# FPGA_misc.net
KiCad netlist of a schematic drawn in Altium Designer
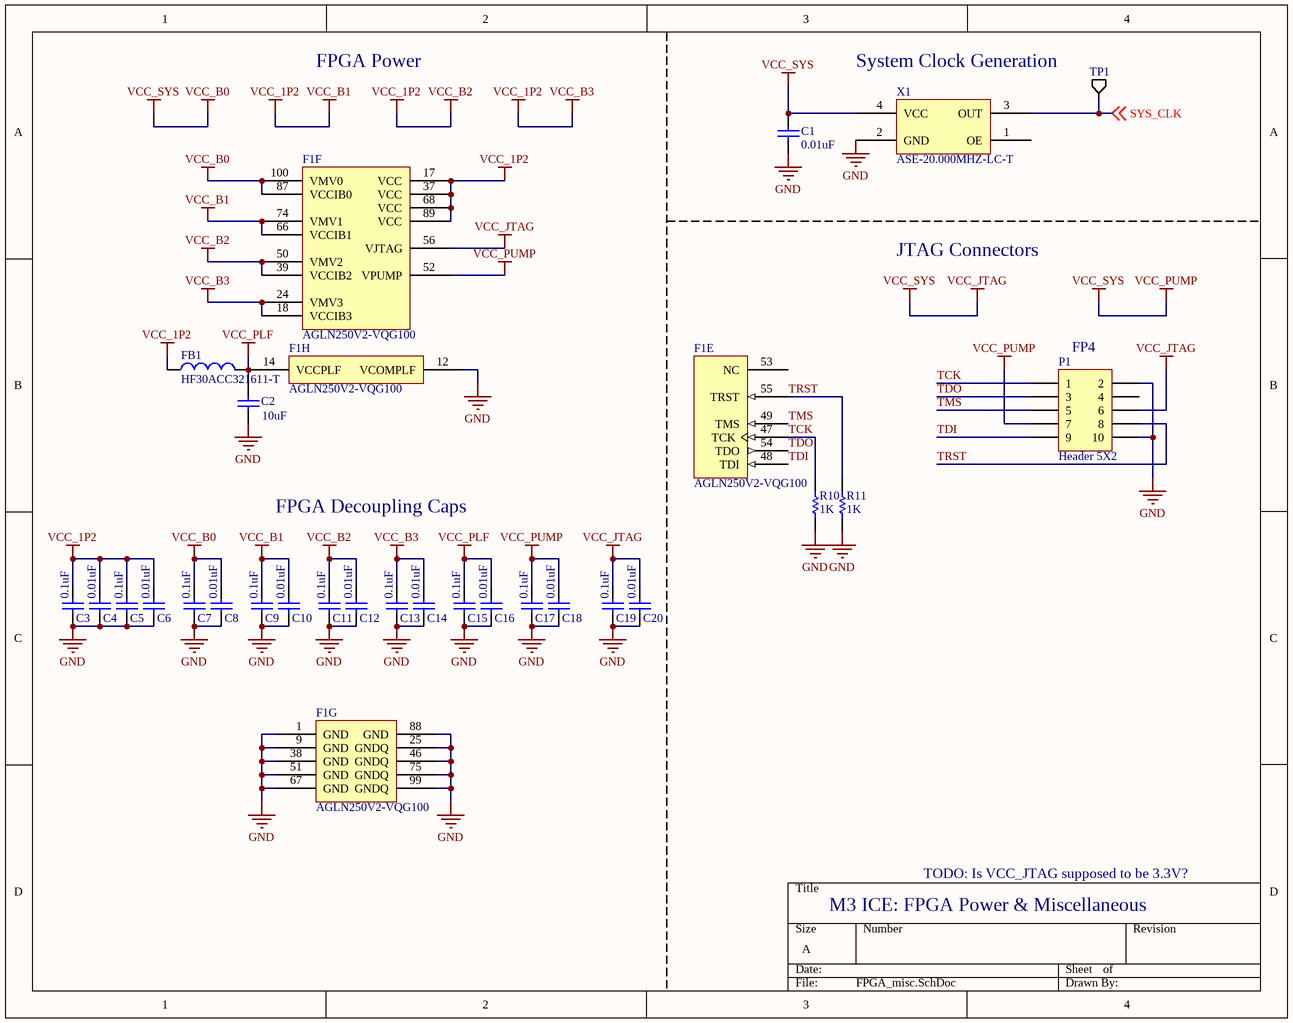
[diagram p0: FPGA_misc.SchDoc]

(export (version "E")
  (design (tool "Eeschema 10.0.6"))
  (components
    (comp (ref "C1")
      (value "0.01uF")
      (footprint "1608[0603]")
      (description "Capacitor (Semiconductor SIM Model)")
      (fields
        (field (name "DISTPARTNO") "445-1311-1-ND")
        (field (name "MANPARTNO") "C1608X7R1H103K")
        (field (name "PUBLISHER") "Altium Limited")
      )
      (libsource (lib "Miscellaneous Devices") (part "Cap Semi"))
    )
    (comp (ref "C2")
      (value "10uF")
      (footprint "0805")
      (description "Capacitor (Semiconductor SIM Model)")
      (fields
        (field (name "DISTPARTNO") "445-7645-1-ND")
        (field (name "MANPARTNO") "C2012X5R1C106M/0.85")
        (field (name "PUBLISHER") "Altium Limited")
      )
      (libsource (lib "M3") (part "Cap Chip"))
    )
    (comp (ref "C3")
      (value "0.1uF")
      (footprint "1608[0603]")
      (description "Capacitor (Semiconductor SIM Model)")
      (fields
        (field (name "DISTPARTNO") "445-1317-1-ND")
        (field (name "MANPARTNO") "C1608X7R1C104K")
        (field (name "PUBLISHER") "Altium Limited")
      )
      (libsource (lib "Miscellaneous Devices") (part "Cap Semi"))
    )
    (comp (ref "C4")
      (value "0.01uF")
      (footprint "1608[0603]")
      (description "Capacitor (Semiconductor SIM Model)")
      (fields
        (field (name "DISTPARTNO") "445-1311-1-ND")
        (field (name "MANPARTNO") "C1608X7R1H103K")
        (field (name "PUBLISHER") "Altium Limited")
      )
      (libsource (lib "Miscellaneous Devices") (part "Cap Semi"))
    )
    (comp (ref "C5")
      (value "0.1uF")
      (footprint "1608[0603]")
      (description "Capacitor (Semiconductor SIM Model)")
      (fields
        (field (name "DISTPARTNO") "445-1317-1-ND")
        (field (name "MANPARTNO") "C1608X7R1C104K")
        (field (name "PUBLISHER") "Altium Limited")
      )
      (libsource (lib "Miscellaneous Devices") (part "Cap Semi"))
    )
    (comp (ref "C6")
      (value "0.01uF")
      (footprint "1608[0603]")
      (description "Capacitor (Semiconductor SIM Model)")
      (fields
        (field (name "DISTPARTNO") "445-1311-1-ND")
        (field (name "MANPARTNO") "C1608X7R1H103K")
        (field (name "PUBLISHER") "Altium Limited")
      )
      (libsource (lib "Miscellaneous Devices") (part "Cap Semi"))
    )
    (comp (ref "C7")
      (value "0.1uF")
      (footprint "1608[0603]")
      (description "Capacitor (Semiconductor SIM Model)")
      (fields
        (field (name "DISTPARTNO") "445-1317-1-ND")
        (field (name "MANPARTNO") "C1608X7R1C104K")
        (field (name "PUBLISHER") "Altium Limited")
      )
      (libsource (lib "Miscellaneous Devices") (part "Cap Semi"))
    )
    (comp (ref "C8")
      (value "0.01uF")
      (footprint "1608[0603]")
      (description "Capacitor (Semiconductor SIM Model)")
      (fields
        (field (name "DISTPARTNO") "445-1311-1-ND")
        (field (name "MANPARTNO") "C1608X7R1H103K")
        (field (name "PUBLISHER") "Altium Limited")
      )
      (libsource (lib "Miscellaneous Devices") (part "Cap Semi"))
    )
    (comp (ref "C9")
      (value "0.1uF")
      (footprint "1608[0603]")
      (description "Capacitor (Semiconductor SIM Model)")
      (fields
        (field (name "DISTPARTNO") "445-1317-1-ND")
        (field (name "MANPARTNO") "C1608X7R1C104K")
        (field (name "PUBLISHER") "Altium Limited")
      )
      (libsource (lib "Miscellaneous Devices") (part "Cap Semi"))
    )
    (comp (ref "C10")
      (value "0.01uF")
      (footprint "1608[0603]")
      (description "Capacitor (Semiconductor SIM Model)")
      (fields
        (field (name "DISTPARTNO") "445-1311-1-ND")
        (field (name "MANPARTNO") "C1608X7R1H103K")
        (field (name "PUBLISHER") "Altium Limited")
      )
      (libsource (lib "Miscellaneous Devices") (part "Cap Semi"))
    )
    (comp (ref "C11")
      (value "0.1uF")
      (footprint "1608[0603]")
      (description "Capacitor (Semiconductor SIM Model)")
      (fields
        (field (name "DISTPARTNO") "445-1317-1-ND")
        (field (name "MANPARTNO") "C1608X7R1C104K")
        (field (name "PUBLISHER") "Altium Limited")
      )
      (libsource (lib "Miscellaneous Devices") (part "Cap Semi"))
    )
    (comp (ref "C12")
      (value "0.01uF")
      (footprint "1608[0603]")
      (description "Capacitor (Semiconductor SIM Model)")
      (fields
        (field (name "DISTPARTNO") "445-1311-1-ND")
        (field (name "MANPARTNO") "C1608X7R1H103K")
        (field (name "PUBLISHER") "Altium Limited")
      )
      (libsource (lib "Miscellaneous Devices") (part "Cap Semi"))
    )
    (comp (ref "C13")
      (value "0.1uF")
      (footprint "1608[0603]")
      (description "Capacitor (Semiconductor SIM Model)")
      (fields
        (field (name "DISTPARTNO") "445-1317-1-ND")
        (field (name "MANPARTNO") "C1608X7R1C104K")
        (field (name "PUBLISHER") "Altium Limited")
      )
      (libsource (lib "Miscellaneous Devices") (part "Cap Semi"))
    )
    (comp (ref "C14")
      (value "0.01uF")
      (footprint "1608[0603]")
      (description "Capacitor (Semiconductor SIM Model)")
      (fields
        (field (name "DISTPARTNO") "445-1311-1-ND")
        (field (name "MANPARTNO") "C1608X7R1H103K")
        (field (name "PUBLISHER") "Altium Limited")
      )
      (libsource (lib "Miscellaneous Devices") (part "Cap Semi"))
    )
    (comp (ref "C15")
      (value "0.1uF")
      (footprint "1608[0603]")
      (description "Capacitor (Semiconductor SIM Model)")
      (fields
        (field (name "DISTPARTNO") "445-1317-1-ND")
        (field (name "MANPARTNO") "C1608X7R1C104K")
        (field (name "PUBLISHER") "Altium Limited")
      )
      (libsource (lib "Miscellaneous Devices") (part "Cap Semi"))
    )
    (comp (ref "C16")
      (value "0.01uF")
      (footprint "1608[0603]")
      (description "Capacitor (Semiconductor SIM Model)")
      (fields
        (field (name "DISTPARTNO") "445-1311-1-ND")
        (field (name "MANPARTNO") "C1608X7R1H103K")
        (field (name "PUBLISHER") "Altium Limited")
      )
      (libsource (lib "Miscellaneous Devices") (part "Cap Semi"))
    )
    (comp (ref "C17")
      (value "0.1uF")
      (footprint "1608[0603]")
      (description "Capacitor (Semiconductor SIM Model)")
      (fields
        (field (name "DISTPARTNO") "445-1317-1-ND")
        (field (name "MANPARTNO") "C1608X7R1C104K")
        (field (name "PUBLISHER") "Altium Limited")
      )
      (libsource (lib "Miscellaneous Devices") (part "Cap Semi"))
    )
    (comp (ref "C18")
      (value "0.01uF")
      (footprint "1608[0603]")
      (description "Capacitor (Semiconductor SIM Model)")
      (fields
        (field (name "DISTPARTNO") "445-1311-1-ND")
        (field (name "MANPARTNO") "C1608X7R1H103K")
        (field (name "PUBLISHER") "Altium Limited")
      )
      (libsource (lib "Miscellaneous Devices") (part "Cap Semi"))
    )
    (comp (ref "C19")
      (value "0.1uF")
      (footprint "1608[0603]")
      (description "Capacitor (Semiconductor SIM Model)")
      (fields
        (field (name "DISTPARTNO") "445-1317-1-ND")
        (field (name "MANPARTNO") "C1608X7R1C104K")
        (field (name "PUBLISHER") "Altium Limited")
      )
      (libsource (lib "Miscellaneous Devices") (part "Cap Semi"))
    )
    (comp (ref "C20")
      (value "0.01uF")
      (footprint "1608[0603]")
      (description "Capacitor (Semiconductor SIM Model)")
      (fields
        (field (name "DISTPARTNO") "445-1311-1-ND")
        (field (name "MANPARTNO") "C1608X7R1H103K")
        (field (name "PUBLISHER") "Altium Limited")
      )
      (libsource (lib "Miscellaneous Devices") (part "Cap Semi"))
    )
    (comp (ref "F1")
      (value "AGLN250V2-VQG100")
      (footprint "VQ100_N")
      (fields (field (name "DISTPARTNO") "1100-1134-ND") (field (name "PUBLISHER") "Altium Limited"))
      (libsource (lib "") (part "AGLN250V2-VQG100_1"))
    )
    (comp (ref "FB1")
      (value "HF30ACC321611-T")
      (footprint "Ferrite_Bead_3.2mm_1.6mm")
      (fields (field (name "DISTPARTNO") "445-6165-1-ND"))
      (libsource (lib "M3") (part "Ferrite Bead HF30ACC321611-T"))
    )
    (comp (ref "P1")
      (value "Header 5X2")
      (footprint "HDR2X5")
      (description "Header, 5-Pin, Dual row")
      (fields (field (name "PUBLISHER") "Altium Limited"))
      (libsource (lib "Miscellaneous Connectors") (part "Header 5X2"))
    )
    (comp (ref "R10")
      (value "1K")
      (footprint "0603")
      (description "Semiconductor Resistor")
      (fields
        (field (name "DISTPARTNO") "P1.0KGCT-ND")
        (field (name "MANPARTNO") "ERJ-3GEYJ102V")
        (field (name "PUBLISHER") "Altium Limited")
      )
      (libsource (lib "M3") (part "Res Chip"))
    )
    (comp (ref "R11")
      (value "1K")
      (footprint "0603")
      (description "Semiconductor Resistor")
      (fields
        (field (name "DISTPARTNO") "P1.0KGCT-ND")
        (field (name "MANPARTNO") "ERJ-3GEYJ102V")
        (field (name "PUBLISHER") "Altium Limited")
      )
      (libsource (lib "M3") (part "Res Chip"))
    )
    (comp (ref "TP1") (value "TP") (footprint "TP") (libsource (lib "M3") (part "TP")))
    (comp (ref "X1")
      (value "ASE-20.000MHZ-LC-T")
      (footprint "CRYSTAL_3.2mm_2.5mm")
      (fields (field (name "DISTPARTNO") "535-9565-1-ND"))
      (libsource (lib "M3") (part "ASE-20.000MHZ-LC-T"))
    )
  )
  (nets
    (net (code "1") (name "/TCK") (class "Default")
      (node (ref "F1") (pin "47") (pinfunction "TCK_47") (pintype "input"))
      (node (ref "P1") (pin "1") (pinfunction "1_1") (pintype "passive"))
      (node (ref "R10") (pin "1") (pinfunction "1_1") (pintype "passive"))
    )
    (net (code "2") (name "/TDI") (class "Default")
      (node (ref "F1") (pin "48") (pinfunction "TDI_48") (pintype "input"))
      (node (ref "P1") (pin "9") (pinfunction "9_9") (pintype "passive"))
    )
    (net (code "3") (name "/TDO") (class "Default")
      (node (ref "F1") (pin "54") (pinfunction "TDO_54") (pintype "output"))
      (node (ref "P1") (pin "3") (pinfunction "3_3") (pintype "passive"))
    )
    (net (code "4") (name "/TMS") (class "Default")
      (node (ref "F1") (pin "49") (pinfunction "TMS_49") (pintype "input"))
      (node (ref "P1") (pin "5") (pinfunction "5_5") (pintype "passive"))
    )
    (net (code "5") (name "/TRST") (class "Default")
      (node (ref "F1") (pin "55") (pinfunction "TRST_55") (pintype "input"))
      (node (ref "P1") (pin "8") (pinfunction "8_8") (pintype "passive"))
      (node (ref "R11") (pin "1") (pinfunction "1_1") (pintype "passive"))
    )
    (net (code "6") (name "GND") (class "Default")
      (node (ref "C1") (pin "1") (pinfunction "1_1") (pintype "passive"))
      (node (ref "C10") (pin "1") (pinfunction "1_1") (pintype "passive"))
      (node (ref "C11") (pin "1") (pinfunction "1_1") (pintype "passive"))
      (node (ref "C12") (pin "1") (pinfunction "1_1") (pintype "passive"))
      (node (ref "C13") (pin "1") (pinfunction "1_1") (pintype "passive"))
      (node (ref "C14") (pin "1") (pinfunction "1_1") (pintype "passive"))
      (node (ref "C15") (pin "1") (pinfunction "1_1") (pintype "passive"))
      (node (ref "C16") (pin "1") (pinfunction "1_1") (pintype "passive"))
      (node (ref "C17") (pin "1") (pinfunction "1_1") (pintype "passive"))
      (node (ref "C18") (pin "1") (pinfunction "1_1") (pintype "passive"))
      (node (ref "C19") (pin "1") (pinfunction "1_1") (pintype "passive"))
      (node (ref "C2") (pin "1") (pinfunction "1_1") (pintype "passive"))
      (node (ref "C20") (pin "1") (pinfunction "1_1") (pintype "passive"))
      (node (ref "C3") (pin "1") (pinfunction "1_1") (pintype "passive"))
      (node (ref "C4") (pin "1") (pinfunction "1_1") (pintype "passive"))
      (node (ref "C5") (pin "1") (pinfunction "1_1") (pintype "passive"))
      (node (ref "C6") (pin "1") (pinfunction "1_1") (pintype "passive"))
      (node (ref "C7") (pin "1") (pinfunction "1_1") (pintype "passive"))
      (node (ref "C8") (pin "1") (pinfunction "1_1") (pintype "passive"))
      (node (ref "C9") (pin "1") (pinfunction "1_1") (pintype "passive"))
      (node (ref "F1") (pin "1") (pinfunction "GND_1") (pintype "power_in"))
      (node (ref "F1") (pin "12") (pinfunction "VCOMPLF_12") (pintype "power_in"))
      (node (ref "F1") (pin "25") (pinfunction "GNDQ_25") (pintype "power_in"))
      (node (ref "F1") (pin "38") (pinfunction "GND_38") (pintype "power_in"))
      (node (ref "F1") (pin "46") (pinfunction "GNDQ_46") (pintype "power_in"))
      (node (ref "F1") (pin "51") (pinfunction "GND_51") (pintype "power_in"))
      (node (ref "F1") (pin "67") (pinfunction "GND_67") (pintype "power_in"))
      (node (ref "F1") (pin "75") (pinfunction "GNDQ_75") (pintype "power_in"))
      (node (ref "F1") (pin "88") (pinfunction "GND_88") (pintype "power_in"))
      (node (ref "F1") (pin "9") (pinfunction "GND_9") (pintype "power_in"))
      (node (ref "F1") (pin "99") (pinfunction "GNDQ_99") (pintype "power_in"))
      (node (ref "P1") (pin "10") (pinfunction "10_10") (pintype "passive"))
      (node (ref "P1") (pin "2") (pinfunction "2_2") (pintype "passive"))
      (node (ref "R10") (pin "2") (pinfunction "2_2") (pintype "passive"))
      (node (ref "R11") (pin "2") (pinfunction "2_2") (pintype "passive"))
      (node (ref "X1") (pin "2") (pinfunction "GND_2") (pintype "passive"))
    )
    (net (code "7") (name "SYS_CLK") (class "Default")
      (node (ref "TP1") (pin "1") (pinfunction "A_1") (pintype "passive"))
      (node (ref "X1") (pin "3") (pinfunction "OUT_3") (pintype "passive"))
    )
    (net (code "8") (name "VCC_1P2") (class "Default")
      (node (ref "C10") (pin "2") (pinfunction "2_2") (pintype "passive"))
      (node (ref "C11") (pin "2") (pinfunction "2_2") (pintype "passive"))
      (node (ref "C12") (pin "2") (pinfunction "2_2") (pintype "passive"))
      (node (ref "C13") (pin "2") (pinfunction "2_2") (pintype "passive"))
      (node (ref "C14") (pin "2") (pinfunction "2_2") (pintype "passive"))
      (node (ref "C3") (pin "2") (pinfunction "2_2") (pintype "passive"))
      (node (ref "C4") (pin "2") (pinfunction "2_2") (pintype "passive"))
      (node (ref "C5") (pin "2") (pinfunction "2_2") (pintype "passive"))
      (node (ref "C6") (pin "2") (pinfunction "2_2") (pintype "passive"))
      (node (ref "C9") (pin "2") (pinfunction "2_2") (pintype "passive"))
      (node (ref "F1") (pin "17") (pinfunction "VCC_17") (pintype "power_in"))
      (node (ref "F1") (pin "18") (pinfunction "VCCIB3_18") (pintype "power_in"))
      (node (ref "F1") (pin "24") (pinfunction "VMV3_24") (pintype "power_in"))
      (node (ref "F1") (pin "37") (pinfunction "VCC_37") (pintype "power_in"))
      (node (ref "F1") (pin "39") (pinfunction "VCCIB2_39") (pintype "power_in"))
      (node (ref "F1") (pin "50") (pinfunction "VMV2_50") (pintype "power_in"))
      (node (ref "F1") (pin "66") (pinfunction "VCCIB1_66") (pintype "power_in"))
      (node (ref "F1") (pin "68") (pinfunction "VCC_68") (pintype "power_in"))
      (node (ref "F1") (pin "74") (pinfunction "VMV1_74") (pintype "power_in"))
      (node (ref "F1") (pin "89") (pinfunction "VCC_89") (pintype "power_in"))
      (node (ref "FB1") (pin "1") (pinfunction "1_1") (pintype "passive"))
    )
    (net (code "9") (name "VCC_B0") (class "Default")
      (node (ref "C1") (pin "2") (pinfunction "2_2") (pintype "passive"))
      (node (ref "C17") (pin "2") (pinfunction "2_2") (pintype "passive"))
      (node (ref "C18") (pin "2") (pinfunction "2_2") (pintype "passive"))
      (node (ref "C19") (pin "2") (pinfunction "2_2") (pintype "passive"))
      (node (ref "C20") (pin "2") (pinfunction "2_2") (pintype "passive"))
      (node (ref "C7") (pin "2") (pinfunction "2_2") (pintype "passive"))
      (node (ref "C8") (pin "2") (pinfunction "2_2") (pintype "passive"))
      (node (ref "F1") (pin "100") (pinfunction "VMV0_100") (pintype "power_in"))
      (node (ref "F1") (pin "52") (pinfunction "VPUMP_52") (pintype "power_in"))
      (node (ref "F1") (pin "56") (pinfunction "VJTAG_56") (pintype "power_in"))
      (node (ref "F1") (pin "87") (pinfunction "VCCIB0_87") (pintype "power_in"))
      (node (ref "P1") (pin "6") (pinfunction "6_6") (pintype "passive"))
      (node (ref "P1") (pin "7") (pinfunction "7_7") (pintype "passive"))
      (node (ref "X1") (pin "4") (pinfunction "VCC_4") (pintype "passive"))
    )
    (net (code "10") (name "VCC_PLF") (class "Default")
      (node (ref "C15") (pin "2") (pinfunction "2_2") (pintype "passive"))
      (node (ref "C16") (pin "2") (pinfunction "2_2") (pintype "passive"))
      (node (ref "C2") (pin "2") (pinfunction "2_2") (pintype "passive"))
      (node (ref "F1") (pin "14") (pinfunction "VCCPLF_14") (pintype "power_in"))
      (node (ref "FB1") (pin "2") (pinfunction "2_2") (pintype "passive"))
    )
    (net (code "11") (name "unconnected-(F1E-NC-Pad53)") (class "Default")
      (node (ref "F1") (pin "53") (pinfunction "NC_53") (pintype "passive"))
    )
    (net (code "12") (name "unconnected-(P1-Pad4)") (class "Default")
      (node (ref "P1") (pin "4") (pinfunction "4_4") (pintype "passive"))
    )
    (net (code "13") (name "unconnected-(X1-OE-Pad1)") (class "Default")
      (node (ref "X1") (pin "1") (pinfunction "OE_1") (pintype "passive"))
    )
  )
)
